# ESP12E.net
KiCad netlist of a schematic drawn in Altium Designer
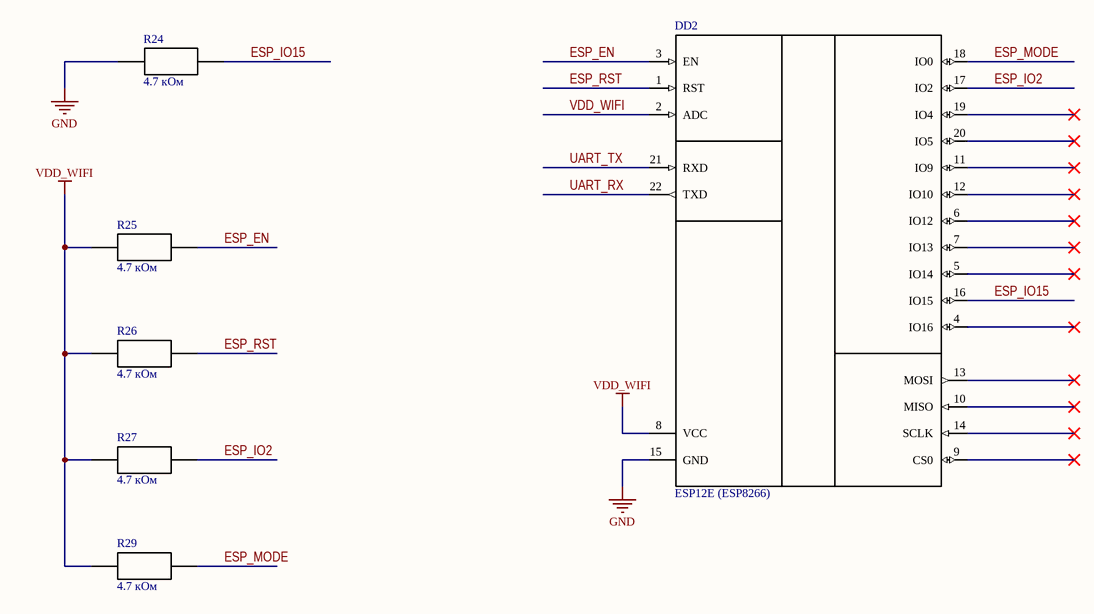
[diagram p0: ESP12E.SchDoc]

(export (version "E")
  (design (tool "Eeschema 10.0.6"))
  (components
    (comp (ref "DD2")
      (value "ESP12E (ESP8266)")
      (footprint "ESP-12E")
      (libsource (lib "my_lib") (part "ESP12E (ESP8266)"))
    )
    (comp (ref "R24") (value "4.7 кОм") (footprint "RES 0805") (libsource (lib "my_lib") (part "RES 0805")))
    (comp (ref "R25") (value "4.7 кОм") (footprint "RES 0805") (libsource (lib "my_lib") (part "RES 0805")))
    (comp (ref "R26") (value "4.7 кОм") (footprint "RES 0805") (libsource (lib "my_lib") (part "RES 0805")))
    (comp (ref "R27") (value "4.7 кОм") (footprint "RES 0805") (libsource (lib "my_lib") (part "RES 0805")))
    (comp (ref "R29") (value "4.7 кОм") (footprint "RES 0805") (libsource (lib "my_lib") (part "RES 0805")))
  )
  (nets
    (net (code "1") (name "/ESP_EN") (class "Default")
      (node (ref "DD2") (pin "3") (pinfunction "EN_3") (pintype "input"))
      (node (ref "R25") (pin "1") (pinfunction "1_1") (pintype "passive"))
    )
    (net (code "2") (name "/ESP_IO2") (class "Default")
      (node (ref "DD2") (pin "17") (pinfunction "IO2_17") (pintype "bidirectional"))
      (node (ref "R27") (pin "1") (pinfunction "1_1") (pintype "passive"))
    )
    (net (code "3") (name "/ESP_IO15") (class "Default")
      (node (ref "DD2") (pin "16") (pinfunction "IO15_16") (pintype "bidirectional"))
      (node (ref "R24") (pin "1") (pinfunction "1_1") (pintype "passive"))
    )
    (net (code "4") (name "/ESP_MODE") (class "Default")
      (node (ref "DD2") (pin "18") (pinfunction "IO0_18") (pintype "bidirectional"))
      (node (ref "R29") (pin "1") (pinfunction "1_1") (pintype "passive"))
    )
    (net (code "5") (name "/ESP_RST") (class "Default")
      (node (ref "DD2") (pin "1") (pinfunction "RST_1") (pintype "input"))
      (node (ref "R26") (pin "1") (pinfunction "1_1") (pintype "passive"))
    )
    (net (code "6") (name "/UART_RX") (class "Default")
      (node (ref "DD2") (pin "22") (pinfunction "TXD_22") (pintype "output"))
    )
    (net (code "7") (name "/UART_TX") (class "Default")
      (node (ref "DD2") (pin "21") (pinfunction "RXD_21") (pintype "input"))
    )
    (net (code "8") (name "GND") (class "Default")
      (node (ref "DD2") (pin "15") (pinfunction "GND_15") (pintype "power_in"))
      (node (ref "R24") (pin "2") (pinfunction "2_2") (pintype "passive"))
    )
    (net (code "9") (name "VDD_WIFI") (class "Default")
      (node (ref "DD2") (pin "2") (pinfunction "ADC_2") (pintype "input"))
      (node (ref "DD2") (pin "8") (pinfunction "VCC_8") (pintype "power_in"))
      (node (ref "R25") (pin "2") (pinfunction "2_2") (pintype "passive"))
      (node (ref "R26") (pin "2") (pinfunction "2_2") (pintype "passive"))
      (node (ref "R27") (pin "2") (pinfunction "2_2") (pintype "passive"))
      (node (ref "R29") (pin "2") (pinfunction "2_2") (pintype "passive"))
    )
    (net (code "10") (name "unconnected-(DD2-CS0-Pad9)") (class "Default")
      (node (ref "DD2") (pin "9") (pinfunction "CS0_9") (pintype "bidirectional+no_connect"))
    )
    (net (code "11") (name "unconnected-(DD2-IO4-Pad19)") (class "Default")
      (node (ref "DD2") (pin "19") (pinfunction "IO4_19") (pintype "bidirectional+no_connect"))
    )
    (net (code "12") (name "unconnected-(DD2-IO5-Pad20)") (class "Default")
      (node (ref "DD2") (pin "20") (pinfunction "IO5_20") (pintype "bidirectional+no_connect"))
    )
    (net (code "13") (name "unconnected-(DD2-IO9-Pad11)") (class "Default")
      (node (ref "DD2") (pin "11") (pinfunction "IO9_11") (pintype "bidirectional+no_connect"))
    )
    (net (code "14") (name "unconnected-(DD2-IO10-Pad12)") (class "Default")
      (node (ref "DD2") (pin "12") (pinfunction "IO10_12") (pintype "bidirectional+no_connect"))
    )
    (net (code "15") (name "unconnected-(DD2-IO12-Pad6)") (class "Default")
      (node (ref "DD2") (pin "6") (pinfunction "IO12_6") (pintype "bidirectional+no_connect"))
    )
    (net (code "16") (name "unconnected-(DD2-IO13-Pad7)") (class "Default")
      (node (ref "DD2") (pin "7") (pinfunction "IO13_7") (pintype "bidirectional+no_connect"))
    )
    (net (code "17") (name "unconnected-(DD2-IO14-Pad5)") (class "Default")
      (node (ref "DD2") (pin "5") (pinfunction "IO14_5") (pintype "bidirectional+no_connect"))
    )
    (net (code "18") (name "unconnected-(DD2-IO16-Pad4)") (class "Default")
      (node (ref "DD2") (pin "4") (pinfunction "IO16_4") (pintype "bidirectional+no_connect"))
    )
    (net (code "19") (name "unconnected-(DD2-MISO-Pad10)") (class "Default")
      (node (ref "DD2") (pin "10") (pinfunction "MISO_10") (pintype "input+no_connect"))
    )
    (net (code "20") (name "unconnected-(DD2-MOSI-Pad13)") (class "Default")
      (node (ref "DD2") (pin "13") (pinfunction "MOSI_13") (pintype "output+no_connect"))
    )
    (net (code "21") (name "unconnected-(DD2-SCLK-Pad14)") (class "Default")
      (node (ref "DD2") (pin "14") (pinfunction "SCLK_14") (pintype "input+no_connect"))
    )
  )
)
